# atmega32u4-aupannel.net
KiCad netlist of a schematic drawn in EAGLE
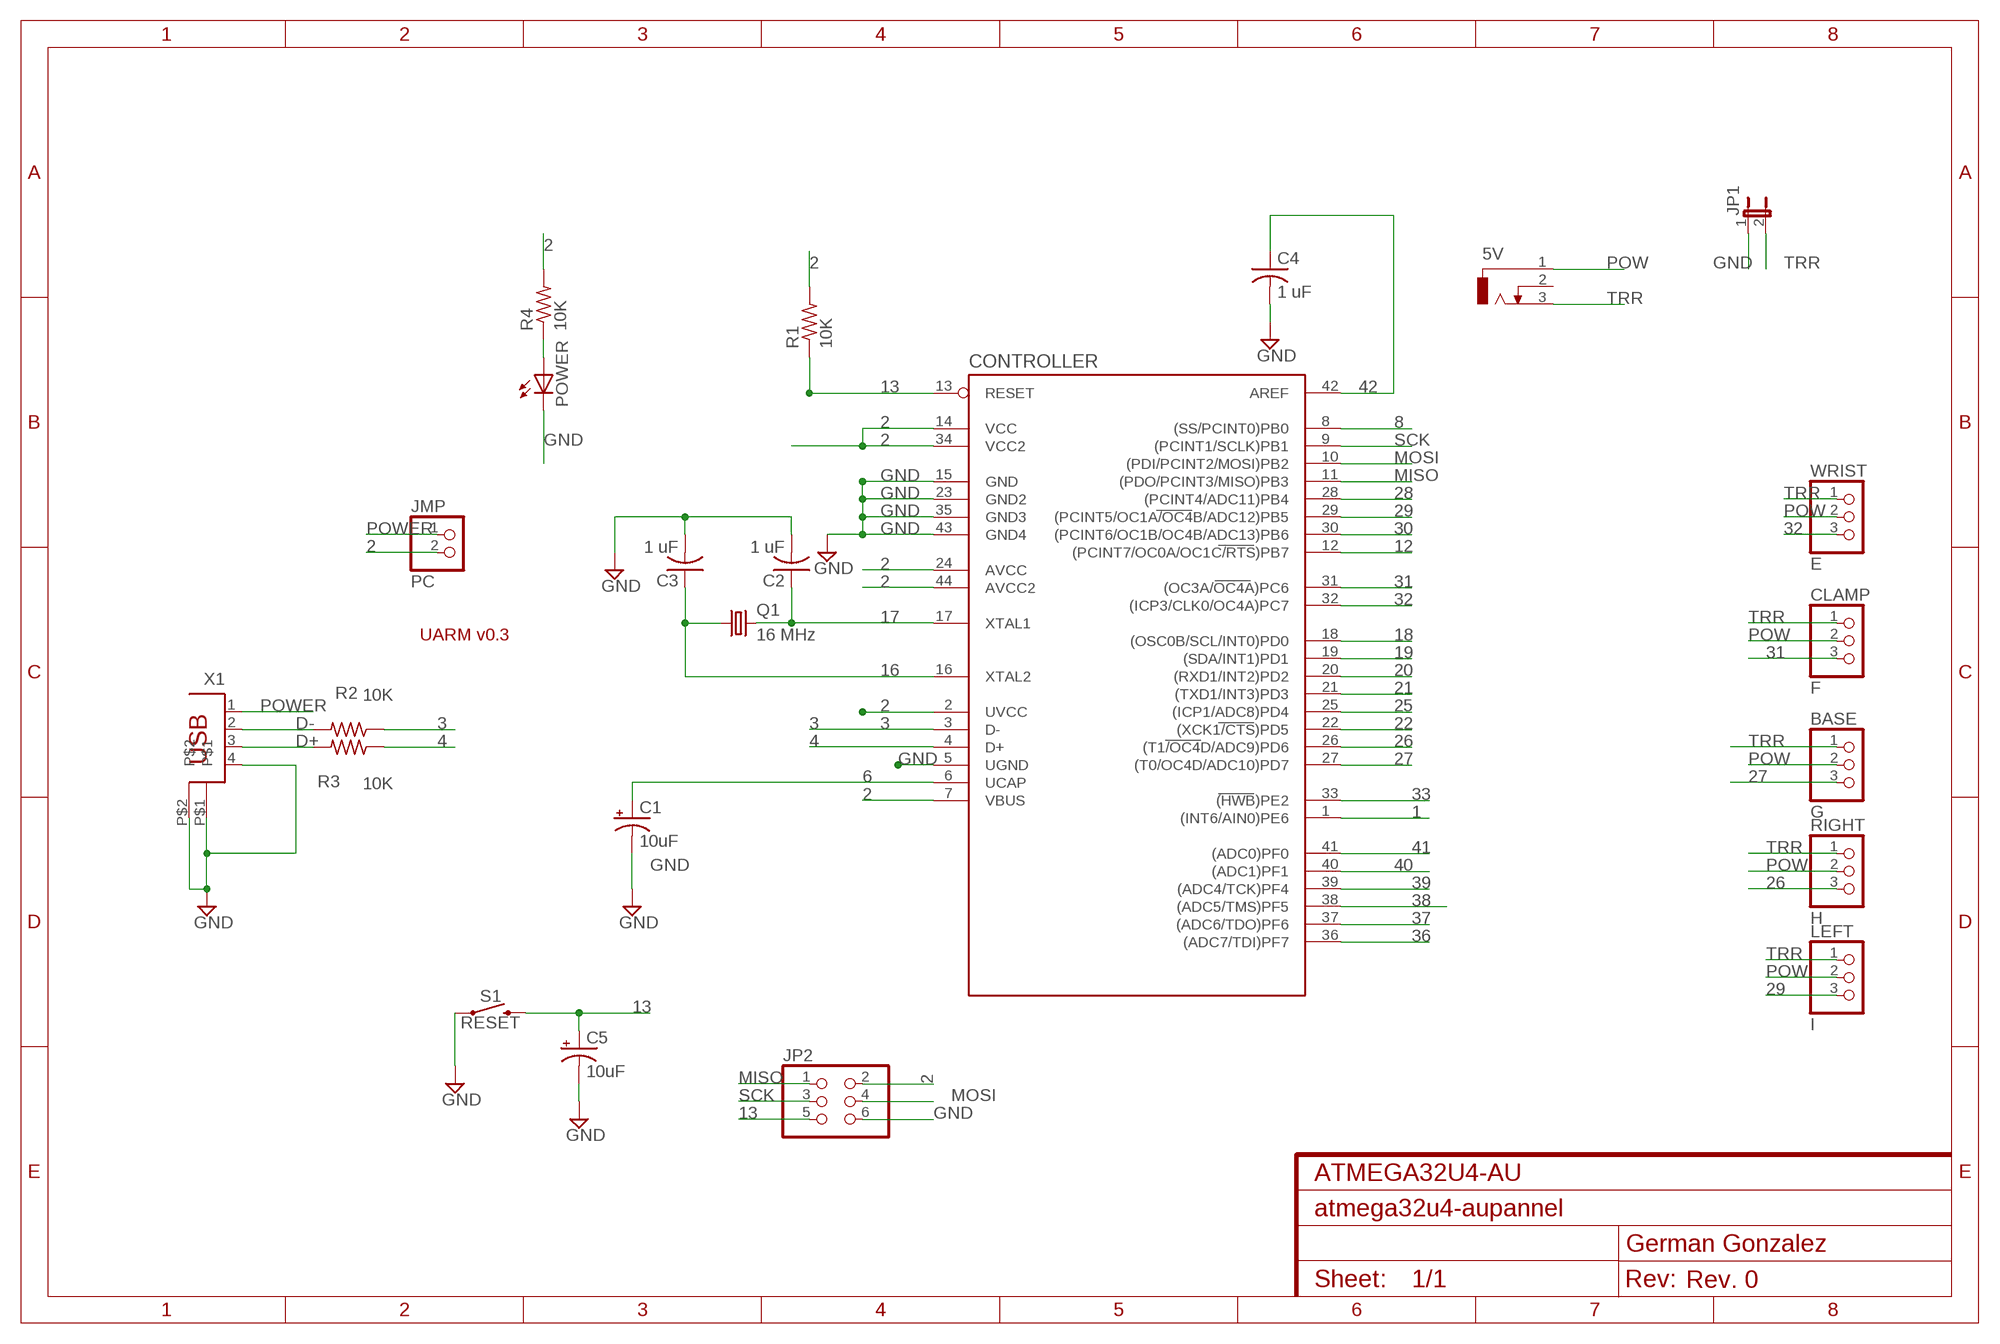
[diagram p0: schematic, sheet 1]

(export (version "E")
  (design (tool "Eeschema 10.0.6"))
  (components
    (comp (ref "5V")
      (value "DCJ0202")
      (footprint "eagle-import:DCJ0202")
      (libsource (lib "eagle-import") (part "DCJ0202"))
    )
    (comp (ref "BASE")
      (value "G")
      (footprint "eagle-import:1X03")
      (libsource (lib "eagle-import") (part "PINHD-1X3"))
    )
    (comp (ref "C1")
      (value "10uF")
      (footprint "eagle-import:CPOL-RADIAL-2.5MM-5MM-KIT")
      (libsource (lib "eagle-import") (part "10UF-POLAR-RADIAL-2.5MM-KIT-25V-20%"))
    )
    (comp (ref "C2")
      (value "1 uF")
      (footprint "eagle-import:C025-024X044")
      (libsource (lib "eagle-import") (part "C-US025-024X044"))
    )
    (comp (ref "C3")
      (value "1 uF")
      (footprint "eagle-import:C025-024X044")
      (libsource (lib "eagle-import") (part "C-US025-024X044"))
    )
    (comp (ref "C4")
      (value "1 uF")
      (footprint "eagle-import:C025-024X044")
      (libsource (lib "eagle-import") (part "C-US025-024X044"))
    )
    (comp (ref "C5")
      (value "10uF")
      (footprint "eagle-import:CPOL-RADIAL-2.5MM-5MM-KIT")
      (libsource (lib "eagle-import") (part "10UF-POLAR-RADIAL-2.5MM-KIT-25V-20%"))
    )
    (comp (ref "CLAMP")
      (value "F")
      (footprint "eagle-import:1X03")
      (libsource (lib "eagle-import") (part "PINHD-1X3"))
    )
    (comp (ref "CONTROLLER")
      (value "ATMEGA32U4-AU")
      (footprint "eagle-import:TQFP44")
      (libsource (lib "eagle-import") (part "ATMEGA32U4-AU"))
    )
    (comp (ref "JMP")
      (value "PC")
      (footprint "eagle-import:1X02")
      (libsource (lib "eagle-import") (part "PINHD-1X2"))
    )
    (comp (ref "JP1")
      (value "JP1E")
      (footprint "eagle-import:JP1")
      (libsource (lib "eagle-import") (part "JP1E"))
    )
    (comp (ref "JP2")
      (value "PINHD-2X3")
      (footprint "eagle-import:2X03")
      (libsource (lib "eagle-import") (part "PINHD-2X3"))
    )
    (comp (ref "LEFT")
      (value "I")
      (footprint "eagle-import:1X03")
      (libsource (lib "eagle-import") (part "PINHD-1X3"))
    )
    (comp (ref "POWER")
      (value "LEDCHIPLED_0805")
      (footprint "eagle-import:CHIPLED_0805")
      (libsource (lib "eagle-import") (part "LEDCHIPLED_0805"))
    )
    (comp (ref "Q1")
      (value "16 MHz")
      (footprint "eagle-import:HC18U-V")
      (libsource (lib "eagle-import") (part "CRYSTALHC18U-V"))
    )
    (comp (ref "R1")
      (value "10K")
      (footprint "eagle-import:M0805")
      (libsource (lib "eagle-import") (part "R-US_M0805"))
    )
    (comp (ref "R2")
      (value "10K")
      (footprint "eagle-import:M0805")
      (libsource (lib "eagle-import") (part "R-US_M0805"))
    )
    (comp (ref "R3")
      (value "10K")
      (footprint "eagle-import:M0805")
      (libsource (lib "eagle-import") (part "R-US_M0805"))
    )
    (comp (ref "R4")
      (value "10K")
      (footprint "eagle-import:M0805")
      (libsource (lib "eagle-import") (part "R-US_M0805"))
    )
    (comp (ref "RIGHT")
      (value "H")
      (footprint "eagle-import:1X03")
      (libsource (lib "eagle-import") (part "PINHD-1X3"))
    )
    (comp (ref "S1")
      (value "RESET")
      (footprint "eagle-import:TACTILE_SWITCH_PTH_6.0MM")
      (libsource (lib "eagle-import") (part "MOMENTARY-SWITCH-SPST-PTH-6.0MM"))
    )
    (comp (ref "WRIST")
      (value "E")
      (footprint "eagle-import:1X03")
      (libsource (lib "eagle-import") (part "PINHD-1X3"))
    )
    (comp (ref "X1")
      (value "PN61729")
      (footprint "eagle-import:PN61729")
      (libsource (lib "eagle-import") (part "PN61729"))
    )
  )
  (nets
    (net (code "1") (name "/1") (class "Default")
      (node (ref "CONTROLLER") (pin "1") (pinfunction "(INT6/AIN0)PE6_1") (pintype "bidirectional"))
    )
    (net (code "2") (name "/2") (class "Default")
      (node (ref "CONTROLLER") (pin "14") (pinfunction "VCC_14") (pintype "bidirectional"))
      (node (ref "CONTROLLER") (pin "2") (pinfunction "UVCC_2") (pintype "bidirectional"))
      (node (ref "CONTROLLER") (pin "24") (pinfunction "AVCC_24") (pintype "bidirectional"))
      (node (ref "CONTROLLER") (pin "34") (pinfunction "VCC2_34") (pintype "bidirectional"))
      (node (ref "CONTROLLER") (pin "44") (pinfunction "AVCC2_44") (pintype "bidirectional"))
      (node (ref "CONTROLLER") (pin "7") (pinfunction "VBUS_7") (pintype "bidirectional"))
      (node (ref "JMP") (pin "2") (pinfunction "2_2") (pintype "passive"))
      (node (ref "JP2") (pin "2") (pinfunction "2_2") (pintype "passive"))
      (node (ref "R1") (pin "2") (pinfunction "2_2") (pintype "passive"))
      (node (ref "R4") (pin "2") (pinfunction "2_2") (pintype "passive"))
    )
    (net (code "3") (name "/3") (class "Default")
      (node (ref "CONTROLLER") (pin "3") (pinfunction "D-_3") (pintype "bidirectional"))
      (node (ref "R2") (pin "1") (pinfunction "1_1") (pintype "passive"))
    )
    (net (code "4") (name "/4") (class "Default")
      (node (ref "CONTROLLER") (pin "4") (pinfunction "D+_4") (pintype "bidirectional"))
      (node (ref "R3") (pin "1") (pinfunction "1_1") (pintype "passive"))
    )
    (net (code "5") (name "/6") (class "Default")
      (node (ref "C1") (pin "1") (pinfunction "+_1") (pintype "passive"))
      (node (ref "CONTROLLER") (pin "6") (pinfunction "UCAP_6") (pintype "bidirectional"))
    )
    (net (code "6") (name "/8") (class "Default")
      (node (ref "CONTROLLER") (pin "8") (pinfunction "(SS/PCINT0)PB0_8") (pintype "bidirectional"))
    )
    (net (code "7") (name "/12") (class "Default")
      (node (ref "CONTROLLER") (pin "12") (pinfunction "(PCINT7/OC0A/OC1C/RTS)PB7_12") (pintype "bidirectional"))
    )
    (net (code "8") (name "/13") (class "Default")
      (node (ref "C5") (pin "1") (pinfunction "+_1") (pintype "passive"))
      (node (ref "CONTROLLER") (pin "13") (pinfunction "RESET_13") (pintype "bidirectional"))
      (node (ref "JP2") (pin "5") (pinfunction "5_5") (pintype "passive"))
      (node (ref "R1") (pin "1") (pinfunction "1_1") (pintype "passive"))
      (node (ref "S1") (pin "3") (pinfunction "2_3") (pintype "passive"))
    )
    (net (code "9") (name "/16") (class "Default")
      (node (ref "C3") (pin "1") (pinfunction "1_1") (pintype "passive"))
      (node (ref "CONTROLLER") (pin "16") (pinfunction "XTAL2_16") (pintype "bidirectional"))
      (node (ref "Q1") (pin "1") (pinfunction "1_1") (pintype "passive"))
    )
    (net (code "10") (name "/17") (class "Default")
      (node (ref "C2") (pin "1") (pinfunction "1_1") (pintype "passive"))
      (node (ref "CONTROLLER") (pin "17") (pinfunction "XTAL1_17") (pintype "bidirectional"))
      (node (ref "Q1") (pin "2") (pinfunction "2_2") (pintype "passive"))
    )
    (net (code "11") (name "/18") (class "Default")
      (node (ref "CONTROLLER") (pin "18") (pinfunction "(OSC0B/SCL/INT0)PD0_18") (pintype "bidirectional"))
    )
    (net (code "12") (name "/19") (class "Default")
      (node (ref "CONTROLLER") (pin "19") (pinfunction "(SDA/INT1)PD1_19") (pintype "bidirectional"))
    )
    (net (code "13") (name "/20") (class "Default")
      (node (ref "CONTROLLER") (pin "20") (pinfunction "(RXD1/INT2)PD2_20") (pintype "bidirectional"))
    )
    (net (code "14") (name "/21") (class "Default")
      (node (ref "CONTROLLER") (pin "21") (pinfunction "(TXD1/INT3)PD3_21") (pintype "bidirectional"))
    )
    (net (code "15") (name "/22") (class "Default")
      (node (ref "CONTROLLER") (pin "22") (pinfunction "(XCK1/CTS)PD5_22") (pintype "bidirectional"))
    )
    (net (code "16") (name "/25") (class "Default")
      (node (ref "CONTROLLER") (pin "25") (pinfunction "(ICP1/ADC8)PD4_25") (pintype "bidirectional"))
    )
    (net (code "17") (name "/26") (class "Default")
      (node (ref "CONTROLLER") (pin "26") (pinfunction "(T1/OC4D/ADC9)PD6_26") (pintype "bidirectional"))
      (node (ref "RIGHT") (pin "3") (pinfunction "3_3") (pintype "passive"))
    )
    (net (code "18") (name "/27") (class "Default")
      (node (ref "BASE") (pin "3") (pinfunction "3_3") (pintype "passive"))
      (node (ref "CONTROLLER") (pin "27") (pinfunction "(T0/OC4D/ADC10)PD7_27") (pintype "bidirectional"))
    )
    (net (code "19") (name "/28") (class "Default")
      (node (ref "CONTROLLER") (pin "28") (pinfunction "(PCINT4/ADC11)PB4_28") (pintype "bidirectional"))
    )
    (net (code "20") (name "/29") (class "Default")
      (node (ref "CONTROLLER") (pin "29") (pinfunction "(PCINT5/OC1A/OC4B/ADC12)PB5_29") (pintype "bidirectional"))
      (node (ref "LEFT") (pin "3") (pinfunction "3_3") (pintype "passive"))
    )
    (net (code "21") (name "/30") (class "Default")
      (node (ref "CONTROLLER") (pin "30") (pinfunction "(PCINT6/OC1B/OC4B/ADC13)PB6_30") (pintype "bidirectional"))
    )
    (net (code "22") (name "/31") (class "Default")
      (node (ref "CLAMP") (pin "3") (pinfunction "3_3") (pintype "passive"))
      (node (ref "CONTROLLER") (pin "31") (pinfunction "(OC3A/OC4A)PC6_31") (pintype "bidirectional"))
    )
    (net (code "23") (name "/32") (class "Default")
      (node (ref "CONTROLLER") (pin "32") (pinfunction "(ICP3/CLK0/OC4A)PC7_32") (pintype "bidirectional"))
      (node (ref "WRIST") (pin "3") (pinfunction "3_3") (pintype "passive"))
    )
    (net (code "24") (name "/33") (class "Default")
      (node (ref "CONTROLLER") (pin "33") (pinfunction "(HWB)PE2_33") (pintype "bidirectional"))
    )
    (net (code "25") (name "/36") (class "Default")
      (node (ref "CONTROLLER") (pin "36") (pinfunction "(ADC7/TDI)PF7_36") (pintype "bidirectional"))
    )
    (net (code "26") (name "/37") (class "Default")
      (node (ref "CONTROLLER") (pin "37") (pinfunction "(ADC6/TDO)PF6_37") (pintype "bidirectional"))
    )
    (net (code "27") (name "/38") (class "Default")
      (node (ref "CONTROLLER") (pin "38") (pinfunction "(ADC5/TMS)PF5_38") (pintype "bidirectional"))
    )
    (net (code "28") (name "/39") (class "Default")
      (node (ref "CONTROLLER") (pin "39") (pinfunction "(ADC4/TCK)PF4_39") (pintype "bidirectional"))
    )
    (net (code "29") (name "/40") (class "Default")
      (node (ref "CONTROLLER") (pin "40") (pinfunction "(ADC1)PF1_40") (pintype "bidirectional"))
    )
    (net (code "30") (name "/41") (class "Default")
      (node (ref "CONTROLLER") (pin "41") (pinfunction "(ADC0)PF0_41") (pintype "bidirectional"))
    )
    (net (code "31") (name "/42") (class "Default")
      (node (ref "C4") (pin "1") (pinfunction "1_1") (pintype "passive"))
      (node (ref "CONTROLLER") (pin "42") (pinfunction "AREF_42") (pintype "bidirectional"))
    )
    (net (code "32") (name "/D+") (class "Default")
      (node (ref "R3") (pin "2") (pinfunction "2_2") (pintype "passive"))
      (node (ref "X1") (pin "3") (pinfunction "3_3") (pintype "bidirectional"))
    )
    (net (code "33") (name "/D-") (class "Default")
      (node (ref "R2") (pin "2") (pinfunction "2_2") (pintype "passive"))
      (node (ref "X1") (pin "2") (pinfunction "2_2") (pintype "bidirectional"))
    )
    (net (code "34") (name "/MISO") (class "Default")
      (node (ref "CONTROLLER") (pin "11") (pinfunction "(PDO/PCINT3/MISO)PB3_11") (pintype "bidirectional"))
      (node (ref "JP2") (pin "1") (pinfunction "1_1") (pintype "passive"))
    )
    (net (code "35") (name "/MOSI") (class "Default")
      (node (ref "CONTROLLER") (pin "10") (pinfunction "(PDI/PCINT2/MOSI)PB2_10") (pintype "bidirectional"))
      (node (ref "JP2") (pin "4") (pinfunction "4_4") (pintype "passive"))
    )
    (net (code "36") (name "/POW") (class "Default")
      (node (ref "5V") (pin "1") (pinfunction "1_1") (pintype "passive"))
      (node (ref "BASE") (pin "2") (pinfunction "2_2") (pintype "passive"))
      (node (ref "CLAMP") (pin "2") (pinfunction "2_2") (pintype "passive"))
      (node (ref "LEFT") (pin "2") (pinfunction "2_2") (pintype "passive"))
      (node (ref "RIGHT") (pin "2") (pinfunction "2_2") (pintype "passive"))
      (node (ref "WRIST") (pin "2") (pinfunction "2_2") (pintype "passive"))
    )
    (net (code "37") (name "/POWER") (class "Default")
      (node (ref "JMP") (pin "1") (pinfunction "1_1") (pintype "passive"))
      (node (ref "X1") (pin "1") (pinfunction "1_1") (pintype "bidirectional"))
    )
    (net (code "38") (name "/SCK") (class "Default")
      (node (ref "CONTROLLER") (pin "9") (pinfunction "(PCINT1/SCLK)PB1_9") (pintype "bidirectional"))
      (node (ref "JP2") (pin "3") (pinfunction "3_3") (pintype "passive"))
    )
    (net (code "39") (name "/TRR") (class "Default")
      (node (ref "5V") (pin "3") (pinfunction "3_3") (pintype "passive"))
      (node (ref "BASE") (pin "1") (pinfunction "1_1") (pintype "passive"))
      (node (ref "CLAMP") (pin "1") (pinfunction "1_1") (pintype "passive"))
      (node (ref "JP1") (pin "2") (pinfunction "2_2") (pintype "passive"))
      (node (ref "LEFT") (pin "1") (pinfunction "1_1") (pintype "passive"))
      (node (ref "RIGHT") (pin "1") (pinfunction "1_1") (pintype "passive"))
      (node (ref "WRIST") (pin "1") (pinfunction "1_1") (pintype "passive"))
    )
    (net (code "40") (name "GND") (class "Default")
      (node (ref "C1") (pin "2") (pinfunction "-_2") (pintype "passive"))
      (node (ref "C2") (pin "2") (pinfunction "2_2") (pintype "passive"))
      (node (ref "C3") (pin "2") (pinfunction "2_2") (pintype "passive"))
      (node (ref "C4") (pin "2") (pinfunction "2_2") (pintype "passive"))
      (node (ref "C5") (pin "2") (pinfunction "-_2") (pintype "passive"))
      (node (ref "CONTROLLER") (pin "15") (pinfunction "GND_15") (pintype "bidirectional"))
      (node (ref "CONTROLLER") (pin "23") (pinfunction "GND2_23") (pintype "bidirectional"))
      (node (ref "CONTROLLER") (pin "35") (pinfunction "GND3_35") (pintype "bidirectional"))
      (node (ref "CONTROLLER") (pin "43") (pinfunction "GND4_43") (pintype "bidirectional"))
      (node (ref "CONTROLLER") (pin "5") (pinfunction "UGND_5") (pintype "bidirectional"))
      (node (ref "JP1") (pin "1") (pinfunction "1_1") (pintype "passive"))
      (node (ref "JP2") (pin "6") (pinfunction "6_6") (pintype "passive"))
      (node (ref "POWER") (pin "C") (pinfunction "C_C") (pintype "passive"))
      (node (ref "S1") (pin "1") (pinfunction "1_1") (pintype "passive"))
      (node (ref "X1") (pin "4") (pinfunction "4_4") (pintype "bidirectional"))
      (node (ref "X1") (pin "P$1") (pinfunction "P$1_P$1") (pintype "bidirectional"))
      (node (ref "X1") (pin "P$2") (pinfunction "P$2_P$2") (pintype "bidirectional"))
    )
    (net (code "41") (name "Net-(POWER-PadA)") (class "Default")
      (node (ref "POWER") (pin "A") (pinfunction "A_A") (pintype "passive"))
      (node (ref "R4") (pin "1") (pinfunction "1_1") (pintype "passive"))
    )
    (net (code "42") (name "unconnected-(5V-Pad2)") (class "Default")
      (node (ref "5V") (pin "2") (pinfunction "2_2") (pintype "passive"))
    )
  )
)
